# EnergyPal_v1_0.net
KiCad netlist of a schematic drawn in EAGLE
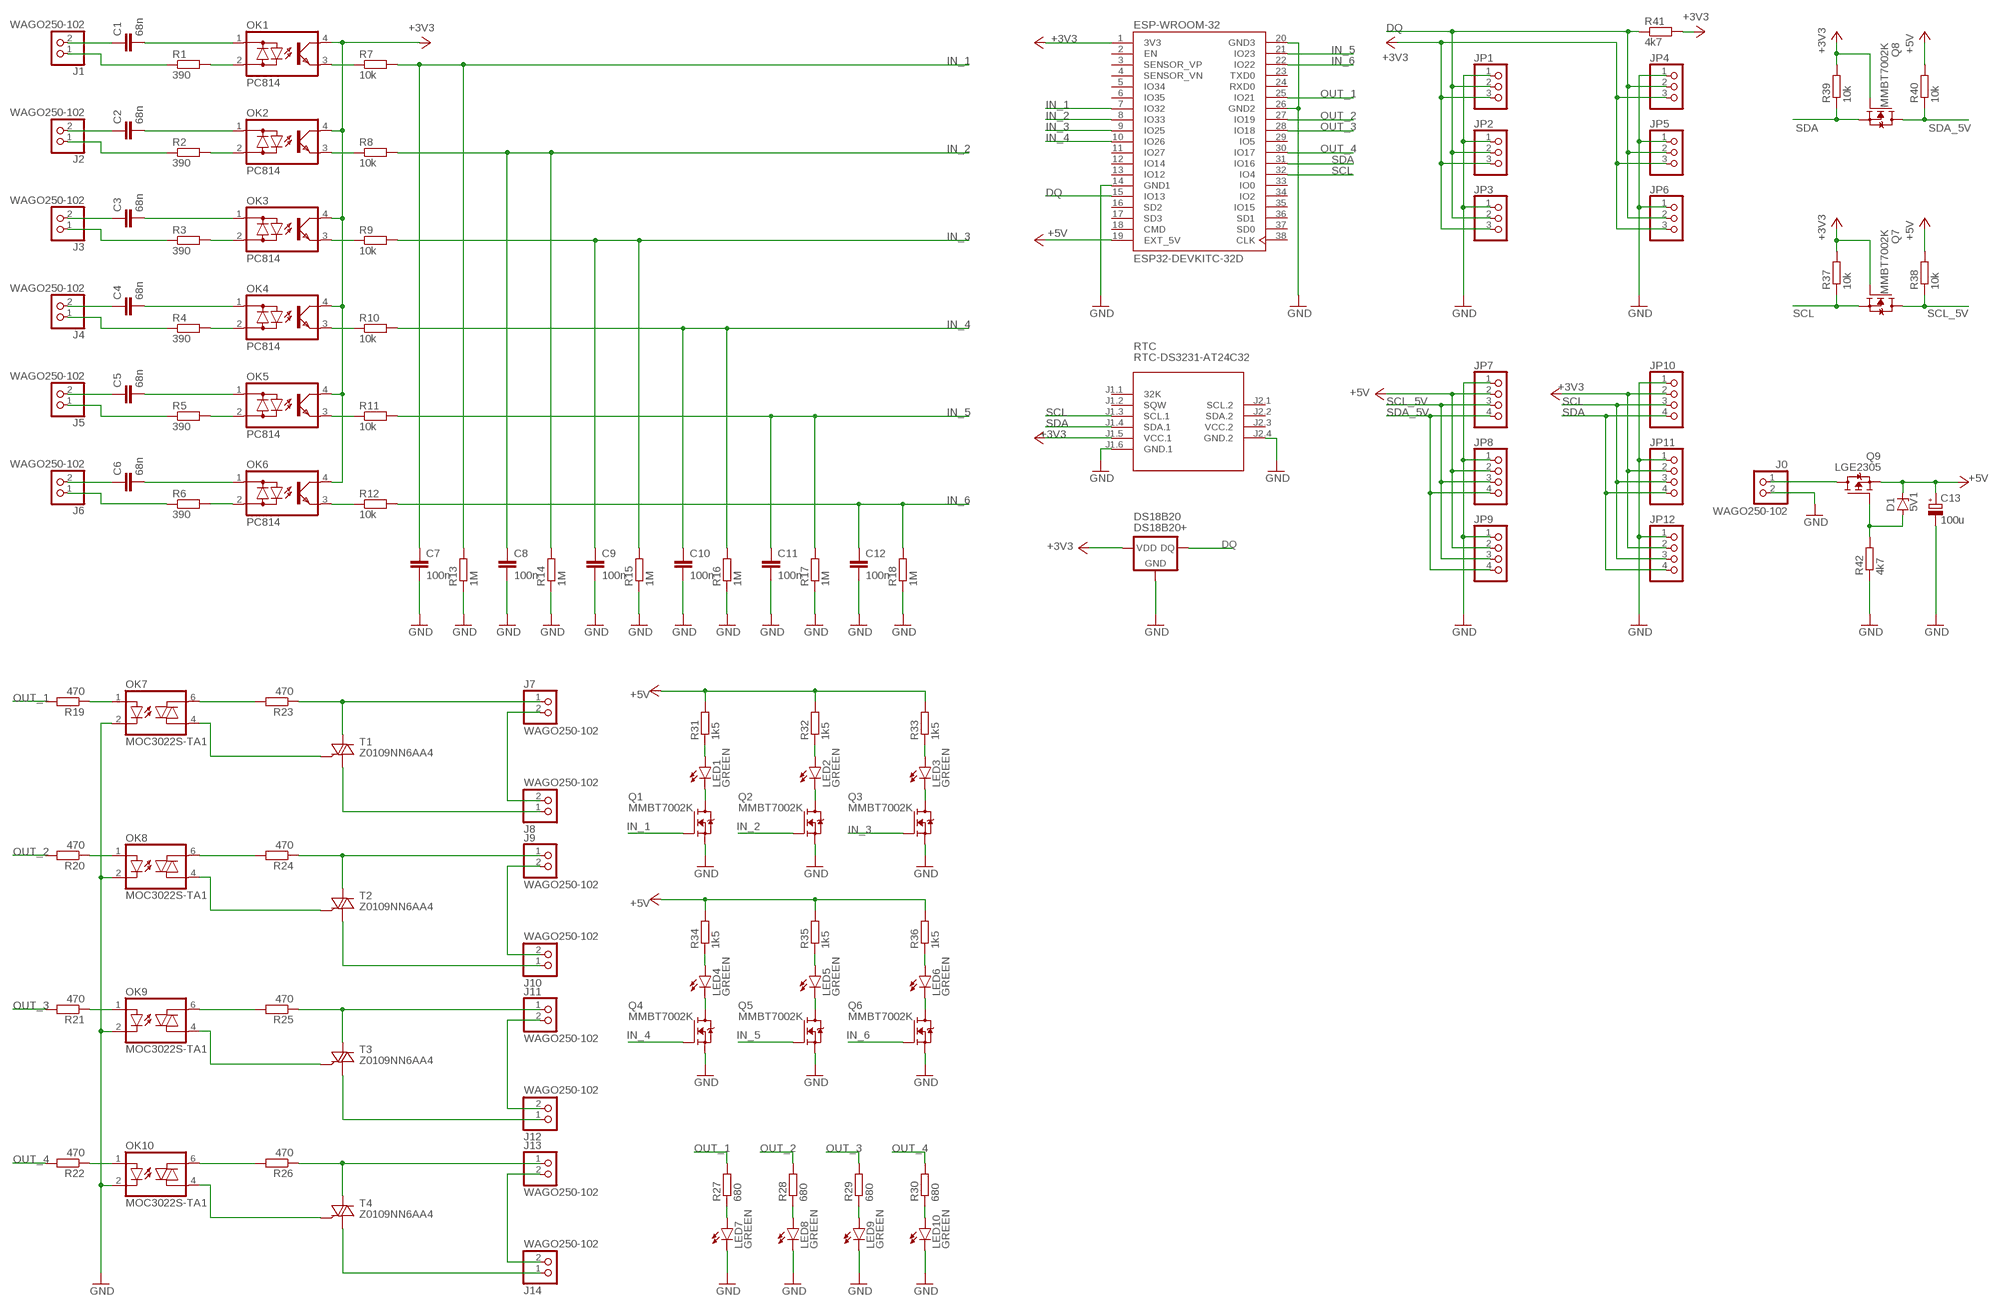
[diagram p0: schematic, sheet 1]

(export (version "E")
  (design (tool "Eeschema 10.0.6"))
  (components
    (comp (ref "C1")
      (value "68n")
      (footprint "eagle-import:C075-063X106")
      (libsource (lib "eagle-import") (part "C-EU075-063X106"))
    )
    (comp (ref "C2")
      (value "68n")
      (footprint "eagle-import:C075-063X106")
      (libsource (lib "eagle-import") (part "C-EU075-063X106"))
    )
    (comp (ref "C3")
      (value "68n")
      (footprint "eagle-import:C075-063X106")
      (libsource (lib "eagle-import") (part "C-EU075-063X106"))
    )
    (comp (ref "C4")
      (value "68n")
      (footprint "eagle-import:C075-063X106")
      (libsource (lib "eagle-import") (part "C-EU075-063X106"))
    )
    (comp (ref "C5")
      (value "68n")
      (footprint "eagle-import:C075-063X106")
      (libsource (lib "eagle-import") (part "C-EU075-063X106"))
    )
    (comp (ref "C6")
      (value "68n")
      (footprint "eagle-import:C075-063X106")
      (libsource (lib "eagle-import") (part "C-EU075-063X106"))
    )
    (comp (ref "C7")
      (value "100n")
      (footprint "eagle-import:C1206")
      (libsource (lib "eagle-import") (part "C-EUC1206"))
    )
    (comp (ref "C8")
      (value "100n")
      (footprint "eagle-import:C1206")
      (libsource (lib "eagle-import") (part "C-EUC1206"))
    )
    (comp (ref "C9")
      (value "100n")
      (footprint "eagle-import:C1206")
      (libsource (lib "eagle-import") (part "C-EUC1206"))
    )
    (comp (ref "C10")
      (value "100n")
      (footprint "eagle-import:C1206")
      (libsource (lib "eagle-import") (part "C-EUC1206"))
    )
    (comp (ref "C11")
      (value "100n")
      (footprint "eagle-import:C1206")
      (libsource (lib "eagle-import") (part "C-EUC1206"))
    )
    (comp (ref "C12")
      (value "100n")
      (footprint "eagle-import:C1206")
      (libsource (lib "eagle-import") (part "C-EUC1206"))
    )
    (comp (ref "C13")
      (value "100u")
      (footprint "eagle-import:UD-6,3X7,7_NICHICON")
      (libsource (lib "eagle-import") (part "CPOL-EUUD-6,3X7,7"))
    )
    (comp (ref "D1")
      (value "5V1")
      (footprint "eagle-import:SOD123")
      (libsource (lib "eagle-import") (part "DDZ9689-7"))
    )
    (comp (ref "DS18B20")
      (value "DS18B20+")
      (footprint "eagle-import:TO92-")
      (libsource (lib "eagle-import") (part "DS18B20+"))
    )
    (comp (ref "ESP-WROOM-32")
      (value "ESP32-DEVKITC-32D")
      (footprint "eagle-import:MODULE_ESP32-DEVKITC-32D")
      (fields (field (name "MF") "Espressif Systems"))
      (libsource (lib "eagle-import") (part "ESP32-DEVKITC-32D"))
    )
    (comp (ref "J0")
      (value "WAGO250-102")
      (footprint "eagle-import:250102")
      (fields (field (name "MANUFACTURER_PART_NUMBER") "250-102"))
      (libsource (lib "eagle-import") (part "WAGO250-102"))
    )
    (comp (ref "J1")
      (value "WAGO250-102")
      (footprint "eagle-import:250102")
      (fields (field (name "MANUFACTURER_PART_NUMBER") "250-102"))
      (libsource (lib "eagle-import") (part "WAGO250-102"))
    )
    (comp (ref "J2")
      (value "WAGO250-102")
      (footprint "eagle-import:250102")
      (fields (field (name "MANUFACTURER_PART_NUMBER") "250-102"))
      (libsource (lib "eagle-import") (part "WAGO250-102"))
    )
    (comp (ref "J3")
      (value "WAGO250-102")
      (footprint "eagle-import:250102")
      (fields (field (name "MANUFACTURER_PART_NUMBER") "250-102"))
      (libsource (lib "eagle-import") (part "WAGO250-102"))
    )
    (comp (ref "J4")
      (value "WAGO250-102")
      (footprint "eagle-import:250102")
      (fields (field (name "MANUFACTURER_PART_NUMBER") "250-102"))
      (libsource (lib "eagle-import") (part "WAGO250-102"))
    )
    (comp (ref "J5")
      (value "WAGO250-102")
      (footprint "eagle-import:250102")
      (fields (field (name "MANUFACTURER_PART_NUMBER") "250-102"))
      (libsource (lib "eagle-import") (part "WAGO250-102"))
    )
    (comp (ref "J6")
      (value "WAGO250-102")
      (footprint "eagle-import:250102")
      (fields (field (name "MANUFACTURER_PART_NUMBER") "250-102"))
      (libsource (lib "eagle-import") (part "WAGO250-102"))
    )
    (comp (ref "J7")
      (value "WAGO250-102")
      (footprint "eagle-import:250102")
      (fields (field (name "MANUFACTURER_PART_NUMBER") "250-102"))
      (libsource (lib "eagle-import") (part "WAGO250-102"))
    )
    (comp (ref "J8")
      (value "WAGO250-102")
      (footprint "eagle-import:250102")
      (fields (field (name "MANUFACTURER_PART_NUMBER") "250-102"))
      (libsource (lib "eagle-import") (part "WAGO250-102"))
    )
    (comp (ref "J9")
      (value "WAGO250-102")
      (footprint "eagle-import:250102")
      (fields (field (name "MANUFACTURER_PART_NUMBER") "250-102"))
      (libsource (lib "eagle-import") (part "WAGO250-102"))
    )
    (comp (ref "J10")
      (value "WAGO250-102")
      (footprint "eagle-import:250102")
      (fields (field (name "MANUFACTURER_PART_NUMBER") "250-102"))
      (libsource (lib "eagle-import") (part "WAGO250-102"))
    )
    (comp (ref "J11")
      (value "WAGO250-102")
      (footprint "eagle-import:250102")
      (fields (field (name "MANUFACTURER_PART_NUMBER") "250-102"))
      (libsource (lib "eagle-import") (part "WAGO250-102"))
    )
    (comp (ref "J12")
      (value "WAGO250-102")
      (footprint "eagle-import:250102")
      (fields (field (name "MANUFACTURER_PART_NUMBER") "250-102"))
      (libsource (lib "eagle-import") (part "WAGO250-102"))
    )
    (comp (ref "J13")
      (value "WAGO250-102")
      (footprint "eagle-import:250102")
      (fields (field (name "MANUFACTURER_PART_NUMBER") "250-102"))
      (libsource (lib "eagle-import") (part "WAGO250-102"))
    )
    (comp (ref "J14")
      (value "WAGO250-102")
      (footprint "eagle-import:250102")
      (fields (field (name "MANUFACTURER_PART_NUMBER") "250-102"))
      (libsource (lib "eagle-import") (part "WAGO250-102"))
    )
    (comp (ref "JP1")
      (value "PINHD-1X3")
      (footprint "eagle-import:1X03")
      (libsource (lib "eagle-import") (part "PINHD-1X3"))
    )
    (comp (ref "JP2")
      (value "PINHD-1X3")
      (footprint "eagle-import:1X03")
      (libsource (lib "eagle-import") (part "PINHD-1X3"))
    )
    (comp (ref "JP3")
      (value "PINHD-1X3")
      (footprint "eagle-import:1X03")
      (libsource (lib "eagle-import") (part "PINHD-1X3"))
    )
    (comp (ref "JP4")
      (value "PINHD-1X3")
      (footprint "eagle-import:1X03")
      (libsource (lib "eagle-import") (part "PINHD-1X3"))
    )
    (comp (ref "JP5")
      (value "PINHD-1X3")
      (footprint "eagle-import:1X03")
      (libsource (lib "eagle-import") (part "PINHD-1X3"))
    )
    (comp (ref "JP6")
      (value "PINHD-1X3")
      (footprint "eagle-import:1X03")
      (libsource (lib "eagle-import") (part "PINHD-1X3"))
    )
    (comp (ref "JP7")
      (value "PINHD-1X4")
      (footprint "eagle-import:1X04")
      (libsource (lib "eagle-import") (part "PINHD-1X4"))
    )
    (comp (ref "JP8")
      (value "PINHD-1X4")
      (footprint "eagle-import:1X04")
      (libsource (lib "eagle-import") (part "PINHD-1X4"))
    )
    (comp (ref "JP9")
      (value "PINHD-1X4")
      (footprint "eagle-import:1X04")
      (libsource (lib "eagle-import") (part "PINHD-1X4"))
    )
    (comp (ref "JP10")
      (value "PINHD-1X4")
      (footprint "eagle-import:1X04")
      (libsource (lib "eagle-import") (part "PINHD-1X4"))
    )
    (comp (ref "JP11")
      (value "PINHD-1X4")
      (footprint "eagle-import:1X04")
      (libsource (lib "eagle-import") (part "PINHD-1X4"))
    )
    (comp (ref "JP12")
      (value "PINHD-1X4")
      (footprint "eagle-import:1X04")
      (libsource (lib "eagle-import") (part "PINHD-1X4"))
    )
    (comp (ref "LED1")
      (value "GREEN")
      (footprint "eagle-import:1206")
      (libsource (lib "eagle-import") (part "LEDSMT1206"))
    )
    (comp (ref "LED2")
      (value "GREEN")
      (footprint "eagle-import:1206")
      (libsource (lib "eagle-import") (part "LEDSMT1206"))
    )
    (comp (ref "LED3")
      (value "GREEN")
      (footprint "eagle-import:1206")
      (libsource (lib "eagle-import") (part "LEDSMT1206"))
    )
    (comp (ref "LED4")
      (value "GREEN")
      (footprint "eagle-import:1206")
      (libsource (lib "eagle-import") (part "LEDSMT1206"))
    )
    (comp (ref "LED5")
      (value "GREEN")
      (footprint "eagle-import:1206")
      (libsource (lib "eagle-import") (part "LEDSMT1206"))
    )
    (comp (ref "LED6")
      (value "GREEN")
      (footprint "eagle-import:1206")
      (libsource (lib "eagle-import") (part "LEDSMT1206"))
    )
    (comp (ref "LED7")
      (value "GREEN")
      (footprint "eagle-import:1206")
      (libsource (lib "eagle-import") (part "LEDSMT1206"))
    )
    (comp (ref "LED8")
      (value "GREEN")
      (footprint "eagle-import:1206")
      (libsource (lib "eagle-import") (part "LEDSMT1206"))
    )
    (comp (ref "LED9")
      (value "GREEN")
      (footprint "eagle-import:1206")
      (libsource (lib "eagle-import") (part "LEDSMT1206"))
    )
    (comp (ref "LED10")
      (value "GREEN")
      (footprint "eagle-import:1206")
      (libsource (lib "eagle-import") (part "LEDSMT1206"))
    )
    (comp (ref "OK1")
      (value "PC814")
      (footprint "eagle-import:SOP254P960X420-4N")
      (libsource (lib "eagle-import") (part "PC814"))
    )
    (comp (ref "OK2")
      (value "PC814")
      (footprint "eagle-import:SOP254P960X420-4N")
      (libsource (lib "eagle-import") (part "PC814"))
    )
    (comp (ref "OK3")
      (value "PC814")
      (footprint "eagle-import:SOP254P960X420-4N")
      (libsource (lib "eagle-import") (part "PC814"))
    )
    (comp (ref "OK4")
      (value "PC814")
      (footprint "eagle-import:SOP254P960X420-4N")
      (libsource (lib "eagle-import") (part "PC814"))
    )
    (comp (ref "OK5")
      (value "PC814")
      (footprint "eagle-import:SOP254P960X420-4N")
      (libsource (lib "eagle-import") (part "PC814"))
    )
    (comp (ref "OK6")
      (value "PC814")
      (footprint "eagle-import:SOP254P960X420-4N")
      (libsource (lib "eagle-import") (part "PC814"))
    )
    (comp (ref "OK7")
      (value "MOC3022S-TA1")
      (footprint "eagle-import:SOP254P1016X460-6N")
      (libsource (lib "eagle-import") (part "MOC3022S-TA1"))
    )
    (comp (ref "OK8")
      (value "MOC3022S-TA1")
      (footprint "eagle-import:SOP254P1016X460-6N")
      (libsource (lib "eagle-import") (part "MOC3022S-TA1"))
    )
    (comp (ref "OK9")
      (value "MOC3022S-TA1")
      (footprint "eagle-import:SOP254P1016X460-6N")
      (libsource (lib "eagle-import") (part "MOC3022S-TA1"))
    )
    (comp (ref "OK10")
      (value "MOC3022S-TA1")
      (footprint "eagle-import:SOP254P1016X460-6N")
      (libsource (lib "eagle-import") (part "MOC3022S-TA1"))
    )
    (comp (ref "Q1")
      (value "MMBT7002K")
      (footprint "eagle-import:SOT23")
      (libsource (lib "eagle-import") (part "MMBT7002K"))
    )
    (comp (ref "Q2")
      (value "MMBT7002K")
      (footprint "eagle-import:SOT23")
      (libsource (lib "eagle-import") (part "MMBT7002K"))
    )
    (comp (ref "Q3")
      (value "MMBT7002K")
      (footprint "eagle-import:SOT23")
      (libsource (lib "eagle-import") (part "MMBT7002K"))
    )
    (comp (ref "Q4")
      (value "MMBT7002K")
      (footprint "eagle-import:SOT23")
      (libsource (lib "eagle-import") (part "MMBT7002K"))
    )
    (comp (ref "Q5")
      (value "MMBT7002K")
      (footprint "eagle-import:SOT23")
      (libsource (lib "eagle-import") (part "MMBT7002K"))
    )
    (comp (ref "Q6")
      (value "MMBT7002K")
      (footprint "eagle-import:SOT23")
      (libsource (lib "eagle-import") (part "MMBT7002K"))
    )
    (comp (ref "Q7")
      (value "MMBT7002K")
      (footprint "eagle-import:SOT23")
      (libsource (lib "eagle-import") (part "MMBT7002K"))
    )
    (comp (ref "Q8")
      (value "MMBT7002K")
      (footprint "eagle-import:SOT23")
      (libsource (lib "eagle-import") (part "MMBT7002K"))
    )
    (comp (ref "Q9")
      (value "LGE2305")
      (footprint "eagle-import:SOT23")
      (libsource (lib "eagle-import") (part "LGE2305"))
    )
    (comp (ref "R1")
      (value "390")
      (footprint "eagle-import:R1206")
      (libsource (lib "eagle-import") (part "R-EU_R1206"))
    )
    (comp (ref "R2")
      (value "390")
      (footprint "eagle-import:R1206")
      (libsource (lib "eagle-import") (part "R-EU_R1206"))
    )
    (comp (ref "R3")
      (value "390")
      (footprint "eagle-import:R1206")
      (libsource (lib "eagle-import") (part "R-EU_R1206"))
    )
    (comp (ref "R4")
      (value "390")
      (footprint "eagle-import:R1206")
      (libsource (lib "eagle-import") (part "R-EU_R1206"))
    )
    (comp (ref "R5")
      (value "390")
      (footprint "eagle-import:R1206")
      (libsource (lib "eagle-import") (part "R-EU_R1206"))
    )
    (comp (ref "R6")
      (value "390")
      (footprint "eagle-import:R1206")
      (libsource (lib "eagle-import") (part "R-EU_R1206"))
    )
    (comp (ref "R7")
      (value "10k")
      (footprint "eagle-import:R1206")
      (libsource (lib "eagle-import") (part "R-EU_R1206"))
    )
    (comp (ref "R8")
      (value "10k")
      (footprint "eagle-import:R1206")
      (libsource (lib "eagle-import") (part "R-EU_R1206"))
    )
    (comp (ref "R9")
      (value "10k")
      (footprint "eagle-import:R1206")
      (libsource (lib "eagle-import") (part "R-EU_R1206"))
    )
    (comp (ref "R10")
      (value "10k")
      (footprint "eagle-import:R1206")
      (libsource (lib "eagle-import") (part "R-EU_R1206"))
    )
    (comp (ref "R11")
      (value "10k")
      (footprint "eagle-import:R1206")
      (libsource (lib "eagle-import") (part "R-EU_R1206"))
    )
    (comp (ref "R12")
      (value "10k")
      (footprint "eagle-import:R1206")
      (libsource (lib "eagle-import") (part "R-EU_R1206"))
    )
    (comp (ref "R13")
      (value "1M")
      (footprint "eagle-import:R1206")
      (libsource (lib "eagle-import") (part "R-EU_R1206"))
    )
    (comp (ref "R14")
      (value "1M")
      (footprint "eagle-import:R1206")
      (libsource (lib "eagle-import") (part "R-EU_R1206"))
    )
    (comp (ref "R15")
      (value "1M")
      (footprint "eagle-import:R1206")
      (libsource (lib "eagle-import") (part "R-EU_R1206"))
    )
    (comp (ref "R16")
      (value "1M")
      (footprint "eagle-import:R1206")
      (libsource (lib "eagle-import") (part "R-EU_R1206"))
    )
    (comp (ref "R17")
      (value "1M")
      (footprint "eagle-import:R1206")
      (libsource (lib "eagle-import") (part "R-EU_R1206"))
    )
    (comp (ref "R18")
      (value "1M")
      (footprint "eagle-import:R1206")
      (libsource (lib "eagle-import") (part "R-EU_R1206"))
    )
    (comp (ref "R19")
      (value "470")
      (footprint "eagle-import:R1206")
      (libsource (lib "eagle-import") (part "R-EU_R1206"))
    )
    (comp (ref "R20")
      (value "470")
      (footprint "eagle-import:R1206")
      (libsource (lib "eagle-import") (part "R-EU_R1206"))
    )
    (comp (ref "R21")
      (value "470")
      (footprint "eagle-import:R1206")
      (libsource (lib "eagle-import") (part "R-EU_R1206"))
    )
    (comp (ref "R22")
      (value "470")
      (footprint "eagle-import:R1206")
      (libsource (lib "eagle-import") (part "R-EU_R1206"))
    )
    (comp (ref "R23")
      (value "470")
      (footprint "eagle-import:R1206")
      (libsource (lib "eagle-import") (part "R-EU_R1206"))
    )
    (comp (ref "R24")
      (value "470")
      (footprint "eagle-import:R1206")
      (libsource (lib "eagle-import") (part "R-EU_R1206"))
    )
    (comp (ref "R25")
      (value "470")
      (footprint "eagle-import:R1206")
      (libsource (lib "eagle-import") (part "R-EU_R1206"))
    )
    (comp (ref "R26")
      (value "470")
      (footprint "eagle-import:R1206")
      (libsource (lib "eagle-import") (part "R-EU_R1206"))
    )
    (comp (ref "R27")
      (value "680")
      (footprint "eagle-import:R1206")
      (libsource (lib "eagle-import") (part "R-EU_R1206"))
    )
    (comp (ref "R28")
      (value "680")
      (footprint "eagle-import:R1206")
      (libsource (lib "eagle-import") (part "R-EU_R1206"))
    )
    (comp (ref "R29")
      (value "680")
      (footprint "eagle-import:R1206")
      (libsource (lib "eagle-import") (part "R-EU_R1206"))
    )
    (comp (ref "R30")
      (value "680")
      (footprint "eagle-import:R1206")
      (libsource (lib "eagle-import") (part "R-EU_R1206"))
    )
    (comp (ref "R31")
      (value "1k5")
      (footprint "eagle-import:R1206")
      (libsource (lib "eagle-import") (part "R-EU_R1206"))
    )
    (comp (ref "R32")
      (value "1k5")
      (footprint "eagle-import:R1206")
      (libsource (lib "eagle-import") (part "R-EU_R1206"))
    )
    (comp (ref "R33")
      (value "1k5")
      (footprint "eagle-import:R1206")
      (libsource (lib "eagle-import") (part "R-EU_R1206"))
    )
    (comp (ref "R34")
      (value "1k5")
      (footprint "eagle-import:R1206")
      (libsource (lib "eagle-import") (part "R-EU_R1206"))
    )
    (comp (ref "R35")
      (value "1k5")
      (footprint "eagle-import:R1206")
      (libsource (lib "eagle-import") (part "R-EU_R1206"))
    )
    (comp (ref "R36")
      (value "1k5")
      (footprint "eagle-import:R1206")
      (libsource (lib "eagle-import") (part "R-EU_R1206"))
    )
    (comp (ref "R37")
      (value "10k")
      (footprint "eagle-import:R1206")
      (libsource (lib "eagle-import") (part "R-EU_R1206"))
    )
    (comp (ref "R38")
      (value "10k")
      (footprint "eagle-import:R1206")
      (libsource (lib "eagle-import") (part "R-EU_R1206"))
    )
    (comp (ref "R39")
      (value "10k")
      (footprint "eagle-import:R1206")
      (libsource (lib "eagle-import") (part "R-EU_R1206"))
    )
    (comp (ref "R40")
      (value "10k")
      (footprint "eagle-import:R1206")
      (libsource (lib "eagle-import") (part "R-EU_R1206"))
    )
    (comp (ref "R41")
      (value "4k7")
      (footprint "eagle-import:R1206")
      (libsource (lib "eagle-import") (part "R-EU_R1206"))
    )
    (comp (ref "R42")
      (value "4k7")
      (footprint "eagle-import:R1206")
      (libsource (lib "eagle-import") (part "R-EU_R1206"))
    )
    (comp (ref "RTC")
      (value "RTC-DS3231-AT24C32")
      (footprint "eagle-import:RTC-DS3231-AT24C32#MIRROR")
      (libsource (lib "eagle-import") (part "RTC-DS3231-AT24C32"))
    )
    (comp (ref "T1")
      (value "Z0109NN6AA4")
      (footprint "eagle-import:SOT230P700X190-4N")
      (libsource (lib "eagle-import") (part "Z0109NN6AA4"))
    )
    (comp (ref "T2")
      (value "Z0109NN6AA4")
      (footprint "eagle-import:SOT230P700X190-4N")
      (libsource (lib "eagle-import") (part "Z0109NN6AA4"))
    )
    (comp (ref "T3")
      (value "Z0109NN6AA4")
      (footprint "eagle-import:SOT230P700X190-4N")
      (libsource (lib "eagle-import") (part "Z0109NN6AA4"))
    )
    (comp (ref "T4")
      (value "Z0109NN6AA4")
      (footprint "eagle-import:SOT230P700X190-4N")
      (libsource (lib "eagle-import") (part "Z0109NN6AA4"))
    )
  )
  (nets
    (net (code "1") (name "+3V3") (class "Default")
      (node (ref "DS18B20") (pin "3") (pinfunction "VDD_3") (pintype "power_in"))
      (node (ref "ESP-WROOM-32") (pin "1") (pinfunction "3V3_1") (pintype "power_in"))
      (node (ref "JP1") (pin "3") (pinfunction "3_3") (pintype "passive"))
      (node (ref "JP10") (pin "2") (pinfunction "2_2") (pintype "passive"))
      (node (ref "JP11") (pin "2") (pinfunction "2_2") (pintype "passive"))
      (node (ref "JP12") (pin "2") (pinfunction "2_2") (pintype "passive"))
      (node (ref "JP2") (pin "3") (pinfunction "3_3") (pintype "passive"))
      (node (ref "JP3") (pin "3") (pinfunction "3_3") (pintype "passive"))
      (node (ref "JP4") (pin "3") (pinfunction "3_3") (pintype "passive"))
      (node (ref "JP5") (pin "3") (pinfunction "3_3") (pintype "passive"))
      (node (ref "JP6") (pin "3") (pinfunction "3_3") (pintype "passive"))
      (node (ref "OK1") (pin "4") (pinfunction "C_4") (pintype "passive"))
      (node (ref "OK2") (pin "4") (pinfunction "C_4") (pintype "passive"))
      (node (ref "OK3") (pin "4") (pinfunction "C_4") (pintype "passive"))
      (node (ref "OK4") (pin "4") (pinfunction "C_4") (pintype "passive"))
      (node (ref "OK5") (pin "4") (pinfunction "C_4") (pintype "passive"))
      (node (ref "OK6") (pin "4") (pinfunction "C_4") (pintype "passive"))
      (node (ref "Q7") (pin "1") (pinfunction "G_1") (pintype "passive"))
      (node (ref "Q8") (pin "1") (pinfunction "G_1") (pintype "passive"))
      (node (ref "R37") (pin "2") (pinfunction "2_2") (pintype "passive"))
      (node (ref "R39") (pin "2") (pinfunction "2_2") (pintype "passive"))
      (node (ref "R41") (pin "2") (pinfunction "2_2") (pintype "passive"))
      (node (ref "RTC") (pin "J1.5") (pinfunction "VCC.1_J1.5") (pintype "power_in"))
    )
    (net (code "2") (name "+5V") (class "Default")
      (node (ref "C13") (pin "+") (pinfunction "+_+") (pintype "passive"))
      (node (ref "D1") (pin "C") (pinfunction "C_C") (pintype "passive"))
      (node (ref "ESP-WROOM-32") (pin "19") (pinfunction "EXT_5V_19") (pintype "power_in"))
      (node (ref "JP7") (pin "2") (pinfunction "2_2") (pintype "passive"))
      (node (ref "JP8") (pin "2") (pinfunction "2_2") (pintype "passive"))
      (node (ref "JP9") (pin "2") (pinfunction "2_2") (pintype "passive"))
      (node (ref "Q9") (pin "2") (pinfunction "S_2") (pintype "passive"))
      (node (ref "R31") (pin "2") (pinfunction "2_2") (pintype "passive"))
      (node (ref "R32") (pin "2") (pinfunction "2_2") (pintype "passive"))
      (node (ref "R33") (pin "2") (pinfunction "2_2") (pintype "passive"))
      (node (ref "R34") (pin "2") (pinfunction "2_2") (pintype "passive"))
      (node (ref "R35") (pin "2") (pinfunction "2_2") (pintype "passive"))
      (node (ref "R36") (pin "2") (pinfunction "2_2") (pintype "passive"))
      (node (ref "R38") (pin "2") (pinfunction "2_2") (pintype "passive"))
      (node (ref "R40") (pin "2") (pinfunction "2_2") (pintype "passive"))
    )
    (net (code "3") (name "/DQ") (class "Default")
      (node (ref "DS18B20") (pin "2") (pinfunction "DQ_2") (pintype "bidirectional"))
      (node (ref "ESP-WROOM-32") (pin "15") (pinfunction "IO13_15") (pintype "bidirectional"))
      (node (ref "JP1") (pin "2") (pinfunction "2_2") (pintype "passive"))
      (node (ref "JP2") (pin "2") (pinfunction "2_2") (pintype "passive"))
      (node (ref "JP3") (pin "2") (pinfunction "2_2") (pintype "passive"))
      (node (ref "JP4") (pin "2") (pinfunction "2_2") (pintype "passive"))
      (node (ref "JP5") (pin "2") (pinfunction "2_2") (pintype "passive"))
      (node (ref "JP6") (pin "2") (pinfunction "2_2") (pintype "passive"))
      (node (ref "R41") (pin "1") (pinfunction "1_1") (pintype "passive"))
    )
    (net (code "4") (name "/IN_1") (class "Default")
      (node (ref "C7") (pin "1") (pinfunction "1_1") (pintype "passive"))
      (node (ref "ESP-WROOM-32") (pin "7") (pinfunction "IO32_7") (pintype "bidirectional"))
      (node (ref "Q1") (pin "1") (pinfunction "G_1") (pintype "passive"))
      (node (ref "R13") (pin "2") (pinfunction "2_2") (pintype "passive"))
      (node (ref "R7") (pin "2") (pinfunction "2_2") (pintype "passive"))
    )
    (net (code "5") (name "/IN_2") (class "Default")
      (node (ref "C8") (pin "1") (pinfunction "1_1") (pintype "passive"))
      (node (ref "ESP-WROOM-32") (pin "8") (pinfunction "IO33_8") (pintype "bidirectional"))
      (node (ref "Q2") (pin "1") (pinfunction "G_1") (pintype "passive"))
      (node (ref "R14") (pin "2") (pinfunction "2_2") (pintype "passive"))
      (node (ref "R8") (pin "2") (pinfunction "2_2") (pintype "passive"))
    )
    (net (code "6") (name "/IN_3") (class "Default")
      (node (ref "C9") (pin "1") (pinfunction "1_1") (pintype "passive"))
      (node (ref "ESP-WROOM-32") (pin "9") (pinfunction "IO25_9") (pintype "bidirectional"))
      (node (ref "Q3") (pin "1") (pinfunction "G_1") (pintype "passive"))
      (node (ref "R15") (pin "2") (pinfunction "2_2") (pintype "passive"))
      (node (ref "R9") (pin "2") (pinfunction "2_2") (pintype "passive"))
    )
    (net (code "7") (name "/IN_4") (class "Default")
      (node (ref "C10") (pin "1") (pinfunction "1_1") (pintype "passive"))
      (node (ref "ESP-WROOM-32") (pin "10") (pinfunction "IO26_10") (pintype "bidirectional"))
      (node (ref "Q4") (pin "1") (pinfunction "G_1") (pintype "passive"))
      (node (ref "R10") (pin "2") (pinfunction "2_2") (pintype "passive"))
      (node (ref "R16") (pin "2") (pinfunction "2_2") (pintype "passive"))
    )
    (net (code "8") (name "/IN_5") (class "Default")
      (node (ref "C11") (pin "1") (pinfunction "1_1") (pintype "passive"))
      (node (ref "ESP-WROOM-32") (pin "21") (pinfunction "IO23_21") (pintype "bidirectional"))
      (node (ref "Q5") (pin "1") (pinfunction "G_1") (pintype "passive"))
      (node (ref "R11") (pin "2") (pinfunction "2_2") (pintype "passive"))
      (node (ref "R17") (pin "2") (pinfunction "2_2") (pintype "passive"))
    )
    (net (code "9") (name "/IN_6") (class "Default")
      (node (ref "C12") (pin "1") (pinfunction "1_1") (pintype "passive"))
      (node (ref "ESP-WROOM-32") (pin "22") (pinfunction "IO22_22") (pintype "bidirectional"))
      (node (ref "Q6") (pin "1") (pinfunction "G_1") (pintype "passive"))
      (node (ref "R12") (pin "2") (pinfunction "2_2") (pintype "passive"))
      (node (ref "R18") (pin "2") (pinfunction "2_2") (pintype "passive"))
    )
    (net (code "10") (name "/OUT_1") (class "Default")
      (node (ref "ESP-WROOM-32") (pin "25") (pinfunction "IO21_25") (pintype "bidirectional"))
      (node (ref "R19") (pin "2") (pinfunction "2_2") (pintype "passive"))
      (node (ref "R27") (pin "2") (pinfunction "2_2") (pintype "passive"))
    )
    (net (code "11") (name "/OUT_2") (class "Default")
      (node (ref "ESP-WROOM-32") (pin "27") (pinfunction "IO19_27") (pintype "bidirectional"))
      (node (ref "R20") (pin "2") (pinfunction "2_2") (pintype "passive"))
      (node (ref "R28") (pin "2") (pinfunction "2_2") (pintype "passive"))
    )
    (net (code "12") (name "/OUT_3") (class "Default")
      (node (ref "ESP-WROOM-32") (pin "28") (pinfunction "IO18_28") (pintype "bidirectional"))
      (node (ref "R21") (pin "2") (pinfunction "2_2") (pintype "passive"))
      (node (ref "R29") (pin "2") (pinfunction "2_2") (pintype "passive"))
    )
    (net (code "13") (name "/OUT_4") (class "Default")
      (node (ref "ESP-WROOM-32") (pin "30") (pinfunction "IO17_30") (pintype "bidirectional"))
      (node (ref "R22") (pin "2") (pinfunction "2_2") (pintype "passive"))
      (node (ref "R30") (pin "2") (pinfunction "2_2") (pintype "passive"))
    )
    (net (code "14") (name "/SCL") (class "Default")
      (node (ref "ESP-WROOM-32") (pin "32") (pinfunction "IO4_32") (pintype "bidirectional"))
      (node (ref "JP10") (pin "3") (pinfunction "3_3") (pintype "passive"))
      (node (ref "JP11") (pin "3") (pinfunction "3_3") (pintype "passive"))
      (node (ref "JP12") (pin "3") (pinfunction "3_3") (pintype "passive"))
      (node (ref "Q7") (pin "2") (pinfunction "S_2") (pintype "passive"))
      (node (ref "R37") (pin "1") (pinfunction "1_1") (pintype "passive"))
      (node (ref "RTC") (pin "J1.3") (pinfunction "SCL.1_J1.3") (pintype "bidirectional"))
    )
    (net (code "15") (name "/SCL_5V") (class "Default")
      (node (ref "JP7") (pin "3") (pinfunction "3_3") (pintype "passive"))
      (node (ref "JP8") (pin "3") (pinfunction "3_3") (pintype "passive"))
      (node (ref "JP9") (pin "3") (pinfunction "3_3") (pintype "passive"))
      (node (ref "Q7") (pin "3") (pinfunction "D_3") (pintype "passive"))
      (node (ref "R38") (pin "1") (pinfunction "1_1") (pintype "passive"))
    )
    (net (code "16") (name "/SDA") (class "Default")
      (node (ref "ESP-WROOM-32") (pin "31") (pinfunction "IO16_31") (pintype "bidirectional"))
      (node (ref "JP10") (pin "4") (pinfunction "4_4") (pintype "passive"))
      (node (ref "JP11") (pin "4") (pinfunction "4_4") (pintype "passive"))
      (node (ref "JP12") (pin "4") (pinfunction "4_4") (pintype "passive"))
      (node (ref "Q8") (pin "2") (pinfunction "S_2") (pintype "passive"))
      (node (ref "R39") (pin "1") (pinfunction "1_1") (pintype "passive"))
      (node (ref "RTC") (pin "J1.4") (pinfunction "SDA.1_J1.4") (pintype "bidirectional"))
    )
    (net (code "17") (name "/SDA_5V") (class "Default")
      (node (ref "JP7") (pin "4") (pinfunction "4_4") (pintype "passive"))
      (node (ref "JP8") (pin "4") (pinfunction "4_4") (pintype "passive"))
      (node (ref "JP9") (pin "4") (pinfunction "4_4") (pintype "passive"))
      (node (ref "Q8") (pin "3") (pinfunction "D_3") (pintype "passive"))
      (node (ref "R40") (pin "1") (pinfunction "1_1") (pintype "passive"))
    )
    (net (code "18") (name "/VCC.2") (class "Default")
      (node (ref "RTC") (pin "J2.3") (pinfunction "VCC.2_J2.3") (pintype "power_in"))
    )
    (net (code "19") (name "GND") (class "Default")
      (node (ref "C10") (pin "2") (pinfunction "2_2") (pintype "passive"))
      (node (ref "C11") (pin "2") (pinfunction "2_2") (pintype "passive"))
      (node (ref "C12") (pin "2") (pinfunction "2_2") (pintype "passive"))
      (node (ref "C13") (pin "-") (pinfunction "-_-") (pintype "passive"))
      (node (ref "C7") (pin "2") (pinfunction "2_2") (pintype "passive"))
      (node (ref "C8") (pin "2") (pinfunction "2_2") (pintype "passive"))
      (node (ref "C9") (pin "2") (pinfunction "2_2") (pintype "passive"))
      (node (ref "DS18B20") (pin "1") (pinfunction "GND_1") (pintype "power_in"))
      (node (ref "ESP-WROOM-32") (pin "14") (pinfunction "GND1_14") (pintype "power_in"))
      (node (ref "ESP-WROOM-32") (pin "20") (pinfunction "GND3_20") (pintype "power_in"))
      (node (ref "ESP-WROOM-32") (pin "26") (pinfunction "GND2_26") (pintype "power_in"))
      (node (ref "J0") (pin "2") (pinfunction "2_2") (pintype "passive"))
      (node (ref "JP1") (pin "1") (pinfunction "1_1") (pintype "passive"))
      (node (ref "JP10") (pin "1") (pinfunction "1_1") (pintype "passive"))
      (node (ref "JP11") (pin "1") (pinfunction "1_1") (pintype "passive"))
      (node (ref "JP12") (pin "1") (pinfunction "1_1") (pintype "passive"))
      (node (ref "JP2") (pin "1") (pinfunction "1_1") (pintype "passive"))
      (node (ref "JP3") (pin "1") (pinfunction "1_1") (pintype "passive"))
      (node (ref "JP4") (pin "1") (pinfunction "1_1") (pintype "passive"))
      (node (ref "JP5") (pin "1") (pinfunction "1_1") (pintype "passive"))
      (node (ref "JP6") (pin "1") (pinfunction "1_1") (pintype "passive"))
      (node (ref "JP7") (pin "1") (pinfunction "1_1") (pintype "passive"))
      (node (ref "JP8") (pin "1") (pinfunction "1_1") (pintype "passive"))
      (node (ref "JP9") (pin "1") (pinfunction "1_1") (pintype "passive"))
      (node (ref "LED10") (pin "C") (pinfunction "C_C") (pintype "passive"))
      (node (ref "LED7") (pin "C") (pinfunction "C_C") (pintype "passive"))
      (node (ref "LED8") (pin "C") (pinfunction "C_C") (pintype "passive"))
      (node (ref "LED9") (pin "C") (pinfunction "C_C") (pintype "passive"))
      (node (ref "OK10") (pin "2") (pinfunction "C_2") (pintype "passive"))
      (node (ref "OK7") (pin "2") (pinfunction "C_2") (pintype "passive"))
      (node (ref "OK8") (pin "2") (pinfunction "C_2") (pintype "passive"))
      (node (ref "OK9") (pin "2") (pinfunction "C_2") (pintype "passive"))
      (node (ref "Q1") (pin "2") (pinfunction "S_2") (pintype "passive"))
      (node (ref "Q2") (pin "2") (pinfunction "S_2") (pintype "passive"))
      (node (ref "Q3") (pin "2") (pinfunction "S_2") (pintype "passive"))
      (node (ref "Q4") (pin "2") (pinfunction "S_2") (pintype "passive"))
      (node (ref "Q5") (pin "2") (pinfunction "S_2") (pintype "passive"))
      (node (ref "Q6") (pin "2") (pinfunction "S_2") (pintype "passive"))
      (node (ref "R13") (pin "1") (pinfunction "1_1") (pintype "passive"))
      (node (ref "R14") (pin "1") (pinfunction "1_1") (pintype "passive"))
      (node (ref "R15") (pin "1") (pinfunction "1_1") (pintype "passive"))
      (node (ref "R16") (pin "1") (pinfunction "1_1") (pintype "passive"))
      (node (ref "R17") (pin "1") (pinfunction "1_1") (pintype "passive"))
      (node (ref "R18") (pin "1") (pinfunction "1_1") (pintype "passive"))
      (node (ref "R42") (pin "1") (pinfunction "1_1") (pintype "passive"))
      (node (ref "RTC") (pin "J1.6") (pinfunction "GND.1_J1.6") (pintype "power_in"))
      (node (ref "RTC") (pin "J2.4") (pinfunction "GND.2_J2.4") (pintype "power_in"))
    )
    (net (code "20") (name "Net-(C1-Pad1)") (class "Default")
      (node (ref "C1") (pin "1") (pinfunction "1_1") (pintype "passive"))
      (node (ref "J1") (pin "2") (pinfunction "2_2") (pintype "passive"))
    )
    (net (code "21") (name "Net-(C2-Pad1)") (class "Default")
      (node (ref "C2") (pin "1") (pinfunction "1_1") (pintype "passive"))
      (node (ref "J2") (pin "2") (pinfunction "2_2") (pintype "passive"))
    )
    (net (code "22") (name "Net-(C3-Pad1)") (class "Default")
      (node (ref "C3") (pin "1") (pinfunction "1_1") (pintype "passive"))
      (node (ref "J3") (pin "2") (pinfunction "2_2") (pintype "passive"))
    )
    (net (code "23") (name "Net-(C4-Pad1)") (class "Default")
      (node (ref "C4") (pin "1") (pinfunction "1_1") (pintype "passive"))
      (node (ref "J4") (pin "2") (pinfunction "2_2") (pintype "passive"))
    )
    (net (code "24") (name "Net-(C5-Pad1)") (class "Default")
      (node (ref "C5") (pin "1") (pinfunction "1_1") (pintype "passive"))
      (node (ref "J5") (pin "2") (pinfunction "2_2") (pintype "passive"))
    )
    (net (code "25") (name "Net-(C6-Pad1)") (class "Default")
      (node (ref "C6") (pin "1") (pinfunction "1_1") (pintype "passive"))
      (node (ref "J6") (pin "2") (pinfunction "2_2") (pintype "passive"))
    )
    (net (code "26") (name "Net-(J1-Pad1)") (class "Default")
      (node (ref "J1") (pin "1") (pinfunction "1_1") (pintype "passive"))
      (node (ref "R1") (pin "1") (pinfunction "1_1") (pintype "passive"))
    )
    (net (code "27") (name "Net-(J2-Pad1)") (class "Default")
      (node (ref "J2") (pin "1") (pinfunction "1_1") (pintype "passive"))
      (node (ref "R2") (pin "1") (pinfunction "1_1") (pintype "passive"))
    )
    (net (code "28") (name "Net-(J3-Pad1)") (class "Default")
      (node (ref "J3") (pin "1") (pinfunction "1_1") (pintype "passive"))
      (node (ref "R3") (pin "1") (pinfunction "1_1") (pintype "passive"))
    )
    (net (code "29") (name "Net-(J4-Pad1)") (class "Default")
      (node (ref "J4") (pin "1") (pinfunction "1_1") (pintype "passive"))
      (node (ref "R4") (pin "1") (pinfunction "1_1") (pintype "passive"))
    )
    (net (code "30") (name "Net-(J5-Pad1)") (class "Default")
      (node (ref "J5") (pin "1") (pinfunction "1_1") (pintype "passive"))
      (node (ref "R5") (pin "1") (pinfunction "1_1") (pintype "passive"))
    )
    (net (code "31") (name "Net-(J6-Pad1)") (class "Default")
      (node (ref "J6") (pin "1") (pinfunction "1_1") (pintype "passive"))
      (node (ref "R6") (pin "1") (pinfunction "1_1") (pintype "passive"))
    )
    (net (code "32") (name "Net-(J7-Pad1)") (class "Default")
      (node (ref "J7") (pin "1") (pinfunction "1_1") (pintype "passive"))
      (node (ref "R23") (pin "1") (pinfunction "1_1") (pintype "passive"))
      (node (ref "T1") (pin "2") (pinfunction "A2_2") (pintype "passive"))
      (node (ref "T1") (pin "4") (pinfunction "A2_4") (pintype "passive"))
    )
    (net (code "33") (name "Net-(J7-Pad2)") (class "Default")
      (node (ref "J7") (pin "2") (pinfunction "2_2") (pintype "passive"))
      (node (ref "J8") (pin "2") (pinfunction "2_2") (pintype "passive"))
    )
    (net (code "34") (name "Net-(J9-Pad1)") (class "Default")
      (node (ref "J9") (pin "1") (pinfunction "1_1") (pintype "passive"))
      (node (ref "R24") (pin "1") (pinfunction "1_1") (pintype "passive"))
      (node (ref "T2") (pin "2") (pinfunction "A2_2") (pintype "passive"))
      (node (ref "T2") (pin "4") (pinfunction "A2_4") (pintype "passive"))
    )
    (net (code "35") (name "Net-(J10-Pad2)") (class "Default")
      (node (ref "J10") (pin "2") (pinfunction "2_2") (pintype "passive"))
      (node (ref "J9") (pin "2") (pinfunction "2_2") (pintype "passive"))
    )
    (net (code "36") (name "Net-(J11-Pad1)") (class "Default")
      (node (ref "J11") (pin "1") (pinfunction "1_1") (pintype "passive"))
      (node (ref "R25") (pin "1") (pinfunction "1_1") (pintype "passive"))
      (node (ref "T3") (pin "2") (pinfunction "A2_2") (pintype "passive"))
      (node (ref "T3") (pin "4") (pinfunction "A2_4") (pintype "passive"))
    )
    (net (code "37") (name "Net-(J11-Pad2)") (class "Default")
      (node (ref "J11") (pin "2") (pinfunction "2_2") (pintype "passive"))
      (node (ref "J12") (pin "2") (pinfunction "2_2") (pintype "passive"))
    )
    (net (code "38") (name "Net-(J13-Pad1)") (class "Default")
      (node (ref "J13") (pin "1") (pinfunction "1_1") (pintype "passive"))
      (node (ref "R26") (pin "1") (pinfunction "1_1") (pintype "passive"))
      (node (ref "T4") (pin "2") (pinfunction "A2_2") (pintype "passive"))
      (node (ref "T4") (pin "4") (pinfunction "A2_4") (pintype "passive"))
    )
    (net (code "39") (name "Net-(J13-Pad2)") (class "Default")
      (node (ref "J13") (pin "2") (pinfunction "2_2") (pintype "passive"))
      (node (ref "J14") (pin "2") (pinfunction "2_2") (pintype "passive"))
    )
    (net (code "40") (name "Net-(LED1-PadA)") (class "Default")
      (node (ref "LED1") (pin "A") (pinfunction "A_A") (pintype "passive"))
      (node (ref "R31") (pin "1") (pinfunction "1_1") (pintype "passive"))
    )
    (net (code "41") (name "Net-(LED2-PadA)") (class "Default")
      (node (ref "LED2") (pin "A") (pinfunction "A_A") (pintype "passive"))
      (node (ref "R32") (pin "1") (pinfunction "1_1") (pintype "passive"))
    )
    (net (code "42") (name "Net-(LED3-PadA)") (class "Default")
      (node (ref "LED3") (pin "A") (pinfunction "A_A") (pintype "passive"))
      (node (ref "R33") (pin "1") (pinfunction "1_1") (pintype "passive"))
    )
    (net (code "43") (name "Net-(LED4-PadA)") (class "Default")
      (node (ref "LED4") (pin "A") (pinfunction "A_A") (pintype "passive"))
      (node (ref "R34") (pin "1") (pinfunction "1_1") (pintype "passive"))
    )
    (net (code "44") (name "Net-(LED5-PadA)") (class "Default")
      (node (ref "LED5") (pin "A") (pinfunction "A_A") (pintype "passive"))
      (node (ref "R35") (pin "1") (pinfunction "1_1") (pintype "passive"))
    )
    (net (code "45") (name "Net-(LED6-PadA)") (class "Default")
      (node (ref "LED6") (pin "A") (pinfunction "A_A") (pintype "passive"))
      (node (ref "R36") (pin "1") (pinfunction "1_1") (pintype "passive"))
    )
    (net (code "46") (name "Net-(LED7-PadA)") (class "Default")
      (node (ref "LED7") (pin "A") (pinfunction "A_A") (pintype "passive"))
      (node (ref "R27") (pin "1") (pinfunction "1_1") (pintype "passive"))
    )
    (net (code "47") (name "Net-(LED8-PadA)") (class "Default")
      (node (ref "LED8") (pin "A") (pinfunction "A_A") (pintype "passive"))
      (node (ref "R28") (pin "1") (pinfunction "1_1") (pintype "passive"))
    )
    (net (code "48") (name "Net-(LED9-PadA)") (class "Default")
      (node (ref "LED9") (pin "A") (pinfunction "A_A") (pintype "passive"))
      (node (ref "R29") (pin "1") (pinfunction "1_1") (pintype "passive"))
    )
    (net (code "49") (name "Net-(LED10-PadA)") (class "Default")
      (node (ref "LED10") (pin "A") (pinfunction "A_A") (pintype "passive"))
      (node (ref "R30") (pin "1") (pinfunction "1_1") (pintype "passive"))
    )
    (net (code "50") (name "Net-(OK1-AC1)") (class "Default")
      (node (ref "C1") (pin "2") (pinfunction "2_2") (pintype "passive"))
      (node (ref "OK1") (pin "1") (pinfunction "AC1_1") (pintype "passive"))
    )
    (net (code "51") (name "Net-(OK1-AC2)") (class "Default")
      (node (ref "OK1") (pin "2") (pinfunction "AC2_2") (pintype "passive"))
      (node (ref "R1") (pin "2") (pinfunction "2_2") (pintype "passive"))
    )
    (net (code "52") (name "Net-(OK1-E)") (class "Default")
      (node (ref "OK1") (pin "3") (pinfunction "E_3") (pintype "passive"))
      (node (ref "R7") (pin "1") (pinfunction "1_1") (pintype "passive"))
    )
    (net (code "53") (name "Net-(OK2-AC1)") (class "Default")
      (node (ref "C2") (pin "2") (pinfunction "2_2") (pintype "passive"))
      (node (ref "OK2") (pin "1") (pinfunction "AC1_1") (pintype "passive"))
    )
    (net (code "54") (name "Net-(OK2-AC2)") (class "Default")
      (node (ref "OK2") (pin "2") (pinfunction "AC2_2") (pintype "passive"))
      (node (ref "R2") (pin "2") (pinfunction "2_2") (pintype "passive"))
    )
    (net (code "55") (name "Net-(OK2-E)") (class "Default")
      (node (ref "OK2") (pin "3") (pinfunction "E_3") (pintype "passive"))
      (node (ref "R8") (pin "1") (pinfunction "1_1") (pintype "passive"))
    )
    (net (code "56") (name "Net-(OK3-AC1)") (class "Default")
      (node (ref "C3") (pin "2") (pinfunction "2_2") (pintype "passive"))
      (node (ref "OK3") (pin "1") (pinfunction "AC1_1") (pintype "passive"))
    )
    (net (code "57") (name "Net-(OK3-AC2)") (class "Default")
      (node (ref "OK3") (pin "2") (pinfunction "AC2_2") (pintype "passive"))
      (node (ref "R3") (pin "2") (pinfunction "2_2") (pintype "passive"))
    )
    (net (code "58") (name "Net-(OK3-E)") (class "Default")
      (node (ref "OK3") (pin "3") (pinfunction "E_3") (pintype "passive"))
      (node (ref "R9") (pin "1") (pinfunction "1_1") (pintype "passive"))
    )
    (net (code "59") (name "Net-(OK4-AC1)") (class "Default")
      (node (ref "C4") (pin "2") (pinfunction "2_2") (pintype "passive"))
      (node (ref "OK4") (pin "1") (pinfunction "AC1_1") (pintype "passive"))
    )
    (net (code "60") (name "Net-(OK4-AC2)") (class "Default")
      (node (ref "OK4") (pin "2") (pinfunction "AC2_2") (pintype "passive"))
      (node (ref "R4") (pin "2") (pinfunction "2_2") (pintype "passive"))
    )
    (net (code "61") (name "Net-(OK4-E)") (class "Default")
      (node (ref "OK4") (pin "3") (pinfunction "E_3") (pintype "passive"))
      (node (ref "R10") (pin "1") (pinfunction "1_1") (pintype "passive"))
    )
    (net (code "62") (name "Net-(OK5-AC1)") (class "Default")
      (node (ref "C5") (pin "2") (pinfunction "2_2") (pintype "passive"))
      (node (ref "OK5") (pin "1") (pinfunction "AC1_1") (pintype "passive"))
    )
    (net (code "63") (name "Net-(OK5-AC2)") (class "Default")
      (node (ref "OK5") (pin "2") (pinfunction "AC2_2") (pintype "passive"))
      (node (ref "R5") (pin "2") (pinfunction "2_2") (pintype "passive"))
    )
    (net (code "64") (name "Net-(OK5-E)") (class "Default")
      (node (ref "OK5") (pin "3") (pinfunction "E_3") (pintype "passive"))
      (node (ref "R11") (pin "1") (pinfunction "1_1") (pintype "passive"))
    )
    (net (code "65") (name "Net-(OK6-AC1)") (class "Default")
      (node (ref "C6") (pin "2") (pinfunction "2_2") (pintype "passive"))
      (node (ref "OK6") (pin "1") (pinfunction "AC1_1") (pintype "passive"))
    )
    (net (code "66") (name "Net-(OK6-AC2)") (class "Default")
      (node (ref "OK6") (pin "2") (pinfunction "AC2_2") (pintype "passive"))
      (node (ref "R6") (pin "2") (pinfunction "2_2") (pintype "passive"))
    )
    (net (code "67") (name "Net-(OK6-E)") (class "Default")
      (node (ref "OK6") (pin "3") (pinfunction "E_3") (pintype "passive"))
      (node (ref "R12") (pin "1") (pinfunction "1_1") (pintype "passive"))
    )
    (net (code "68") (name "Net-(OK7-A)") (class "Default")
      (node (ref "OK7") (pin "1") (pinfunction "A_1") (pintype "passive"))
      (node (ref "R19") (pin "1") (pinfunction "1_1") (pintype "passive"))
    )
    (net (code "69") (name "Net-(OK7-A1)") (class "Default")
      (node (ref "OK7") (pin "4") (pinfunction "A1_4") (pintype "passive"))
      (node (ref "T1") (pin "3") (pinfunction "G_3") (pintype "passive"))
    )
    (net (code "70") (name "Net-(OK7-A2)") (class "Default")
      (node (ref "OK7") (pin "6") (pinfunction "A2_6") (pintype "passive"))
      (node (ref "R23") (pin "2") (pinfunction "2_2") (pintype "passive"))
    )
    (net (code "71") (name "Net-(OK8-A)") (class "Default")
      (node (ref "OK8") (pin "1") (pinfunction "A_1") (pintype "passive"))
      (node (ref "R20") (pin "1") (pinfunction "1_1") (pintype "passive"))
    )
    (net (code "72") (name "Net-(OK8-A1)") (class "Default")
      (node (ref "OK8") (pin "4") (pinfunction "A1_4") (pintype "passive"))
      (node (ref "T2") (pin "3") (pinfunction "G_3") (pintype "passive"))
    )
    (net (code "73") (name "Net-(OK8-A2)") (class "Default")
      (node (ref "OK8") (pin "6") (pinfunction "A2_6") (pintype "passive"))
      (node (ref "R24") (pin "2") (pinfunction "2_2") (pintype "passive"))
    )
    (net (code "74") (name "Net-(OK9-A)") (class "Default")
      (node (ref "OK9") (pin "1") (pinfunction "A_1") (pintype "passive"))
      (node (ref "R21") (pin "1") (pinfunction "1_1") (pintype "passive"))
    )
    (net (code "75") (name "Net-(OK9-A1)") (class "Default")
      (node (ref "OK9") (pin "4") (pinfunction "A1_4") (pintype "passive"))
      (node (ref "T3") (pin "3") (pinfunction "G_3") (pintype "passive"))
    )
    (net (code "76") (name "Net-(OK9-A2)") (class "Default")
      (node (ref "OK9") (pin "6") (pinfunction "A2_6") (pintype "passive"))
      (node (ref "R25") (pin "2") (pinfunction "2_2") (pintype "passive"))
    )
    (net (code "77") (name "Net-(OK10-A)") (class "Default")
      (node (ref "OK10") (pin "1") (pinfunction "A_1") (pintype "passive"))
      (node (ref "R22") (pin "1") (pinfunction "1_1") (pintype "passive"))
    )
    (net (code "78") (name "Net-(OK10-A1)") (class "Default")
      (node (ref "OK10") (pin "4") (pinfunction "A1_4") (pintype "passive"))
      (node (ref "T4") (pin "3") (pinfunction "G_3") (pintype "passive"))
    )
    (net (code "79") (name "Net-(OK10-A2)") (class "Default")
      (node (ref "OK10") (pin "6") (pinfunction "A2_6") (pintype "passive"))
      (node (ref "R26") (pin "2") (pinfunction "2_2") (pintype "passive"))
    )
    (net (code "80") (name "Net-(Q1-D)") (class "Default")
      (node (ref "LED1") (pin "C") (pinfunction "C_C") (pintype "passive"))
      (node (ref "Q1") (pin "3") (pinfunction "D_3") (pintype "passive"))
    )
    (net (code "81") (name "Net-(Q2-D)") (class "Default")
      (node (ref "LED2") (pin "C") (pinfunction "C_C") (pintype "passive"))
      (node (ref "Q2") (pin "3") (pinfunction "D_3") (pintype "passive"))
    )
    (net (code "82") (name "Net-(Q3-D)") (class "Default")
      (node (ref "LED3") (pin "C") (pinfunction "C_C") (pintype "passive"))
      (node (ref "Q3") (pin "3") (pinfunction "D_3") (pintype "passive"))
    )
    (net (code "83") (name "Net-(Q4-D)") (class "Default")
      (node (ref "LED4") (pin "C") (pinfunction "C_C") (pintype "passive"))
      (node (ref "Q4") (pin "3") (pinfunction "D_3") (pintype "passive"))
    )
    (net (code "84") (name "Net-(Q5-D)") (class "Default")
      (node (ref "LED5") (pin "C") (pinfunction "C_C") (pintype "passive"))
      (node (ref "Q5") (pin "3") (pinfunction "D_3") (pintype "passive"))
    )
    (net (code "85") (name "Net-(Q6-D)") (class "Default")
      (node (ref "LED6") (pin "C") (pinfunction "C_C") (pintype "passive"))
      (node (ref "Q6") (pin "3") (pinfunction "D_3") (pintype "passive"))
    )
    (net (code "86") (name "Net-(Q9-D)") (class "Default")
      (node (ref "J0") (pin "1") (pinfunction "1_1") (pintype "passive"))
      (node (ref "Q9") (pin "3") (pinfunction "D_3") (pintype "passive"))
    )
    (net (code "87") (name "Net-(Q9-G)") (class "Default")
      (node (ref "D1") (pin "A") (pinfunction "A_A") (pintype "passive"))
      (node (ref "Q9") (pin "1") (pinfunction "G_1") (pintype "passive"))
      (node (ref "R42") (pin "2") (pinfunction "2_2") (pintype "passive"))
    )
    (net (code "88") (name "Net-(T1-A1)") (class "Default")
      (node (ref "J8") (pin "1") (pinfunction "1_1") (pintype "passive"))
      (node (ref "T1") (pin "1") (pinfunction "A1_1") (pintype "passive"))
    )
    (net (code "89") (name "Net-(T2-A1)") (class "Default")
      (node (ref "J10") (pin "1") (pinfunction "1_1") (pintype "passive"))
      (node (ref "T2") (pin "1") (pinfunction "A1_1") (pintype "passive"))
    )
    (net (code "90") (name "Net-(T3-A1)") (class "Default")
      (node (ref "J12") (pin "1") (pinfunction "1_1") (pintype "passive"))
      (node (ref "T3") (pin "1") (pinfunction "A1_1") (pintype "passive"))
    )
    (net (code "91") (name "Net-(T4-A1)") (class "Default")
      (node (ref "J14") (pin "1") (pinfunction "1_1") (pintype "passive"))
      (node (ref "T4") (pin "1") (pinfunction "A1_1") (pintype "passive"))
    )
    (net (code "92") (name "unconnected-(ESP-WROOM-32-CLK-Pad38)") (class "Default")
      (node (ref "ESP-WROOM-32") (pin "38") (pinfunction "CLK_38") (pintype "input"))
    )
    (net (code "93") (name "unconnected-(ESP-WROOM-32-CMD-Pad18)") (class "Default")
      (node (ref "ESP-WROOM-32") (pin "18") (pinfunction "CMD_18") (pintype "bidirectional"))
    )
    (net (code "94") (name "unconnected-(ESP-WROOM-32-EN-Pad2)") (class "Default")
      (node (ref "ESP-WROOM-32") (pin "2") (pinfunction "EN_2") (pintype "input"))
    )
    (net (code "95") (name "unconnected-(ESP-WROOM-32-IO0-Pad33)") (class "Default")
      (node (ref "ESP-WROOM-32") (pin "33") (pinfunction "IO0_33") (pintype "bidirectional"))
    )
    (net (code "96") (name "unconnected-(ESP-WROOM-32-IO2-Pad34)") (class "Default")
      (node (ref "ESP-WROOM-32") (pin "34") (pinfunction "IO2_34") (pintype "bidirectional"))
    )
    (net (code "97") (name "unconnected-(ESP-WROOM-32-IO5-Pad29)") (class "Default")
      (node (ref "ESP-WROOM-32") (pin "29") (pinfunction "IO5_29") (pintype "bidirectional"))
    )
    (net (code "98") (name "unconnected-(ESP-WROOM-32-IO12-Pad13)") (class "Default")
      (node (ref "ESP-WROOM-32") (pin "13") (pinfunction "IO12_13") (pintype "bidirectional"))
    )
    (net (code "99") (name "unconnected-(ESP-WROOM-32-IO14-Pad12)") (class "Default")
      (node (ref "ESP-WROOM-32") (pin "12") (pinfunction "IO14_12") (pintype "bidirectional"))
    )
    (net (code "100") (name "unconnected-(ESP-WROOM-32-IO15-Pad35)") (class "Default")
      (node (ref "ESP-WROOM-32") (pin "35") (pinfunction "IO15_35") (pintype "bidirectional"))
    )
    (net (code "101") (name "unconnected-(ESP-WROOM-32-IO27-Pad11)") (class "Default")
      (node (ref "ESP-WROOM-32") (pin "11") (pinfunction "IO27_11") (pintype "bidirectional"))
    )
    (net (code "102") (name "unconnected-(ESP-WROOM-32-IO34-Pad5)") (class "Default")
      (node (ref "ESP-WROOM-32") (pin "5") (pinfunction "IO34_5") (pintype "bidirectional"))
    )
    (net (code "103") (name "unconnected-(ESP-WROOM-32-IO35-Pad6)") (class "Default")
      (node (ref "ESP-WROOM-32") (pin "6") (pinfunction "IO35_6") (pintype "bidirectional"))
    )
    (net (code "104") (name "unconnected-(ESP-WROOM-32-RXD0-Pad24)") (class "Default")
      (node (ref "ESP-WROOM-32") (pin "24") (pinfunction "RXD0_24") (pintype "input"))
    )
    (net (code "105") (name "unconnected-(ESP-WROOM-32-SD0-Pad37)") (class "Default")
      (node (ref "ESP-WROOM-32") (pin "37") (pinfunction "SD0_37") (pintype "bidirectional"))
    )
    (net (code "106") (name "unconnected-(ESP-WROOM-32-SD1-Pad36)") (class "Default")
      (node (ref "ESP-WROOM-32") (pin "36") (pinfunction "SD1_36") (pintype "bidirectional"))
    )
    (net (code "107") (name "unconnected-(ESP-WROOM-32-SD2-Pad16)") (class "Default")
      (node (ref "ESP-WROOM-32") (pin "16") (pinfunction "SD2_16") (pintype "bidirectional"))
    )
    (net (code "108") (name "unconnected-(ESP-WROOM-32-SD3-Pad17)") (class "Default")
      (node (ref "ESP-WROOM-32") (pin "17") (pinfunction "SD3_17") (pintype "bidirectional"))
    )
    (net (code "109") (name "unconnected-(ESP-WROOM-32-SENSOR_VN-Pad4)") (class "Default")
      (node (ref "ESP-WROOM-32") (pin "4") (pinfunction "SENSOR_VN_4") (pintype "input"))
    )
    (net (code "110") (name "unconnected-(ESP-WROOM-32-SENSOR_VP-Pad3)") (class "Default")
      (node (ref "ESP-WROOM-32") (pin "3") (pinfunction "SENSOR_VP_3") (pintype "input"))
    )
    (net (code "111") (name "unconnected-(ESP-WROOM-32-TXD0-Pad23)") (class "Default")
      (node (ref "ESP-WROOM-32") (pin "23") (pinfunction "TXD0_23") (pintype "output"))
    )
    (net (code "112") (name "unconnected-(RTC-32K-PadJ1.1)") (class "Default")
      (node (ref "RTC") (pin "J1.1") (pinfunction "32K_J1.1") (pintype "bidirectional"))
    )
    (net (code "113") (name "unconnected-(RTC-SCL.2-PadJ2.1)") (class "Default")
      (node (ref "RTC") (pin "J2.1") (pinfunction "SCL.2_J2.1") (pintype "bidirectional"))
    )
    (net (code "114") (name "unconnected-(RTC-SDA.2-PadJ2.2)") (class "Default")
      (node (ref "RTC") (pin "J2.2") (pinfunction "SDA.2_J2.2") (pintype "bidirectional"))
    )
    (net (code "115") (name "unconnected-(RTC-SQW-PadJ1.2)") (class "Default")
      (node (ref "RTC") (pin "J1.2") (pinfunction "SQW_J1.2") (pintype "bidirectional"))
    )
  )
)
